# esp32-devkit-evse_2023-04-27.net
KiCad netlist of a schematic drawn in Altium Designer
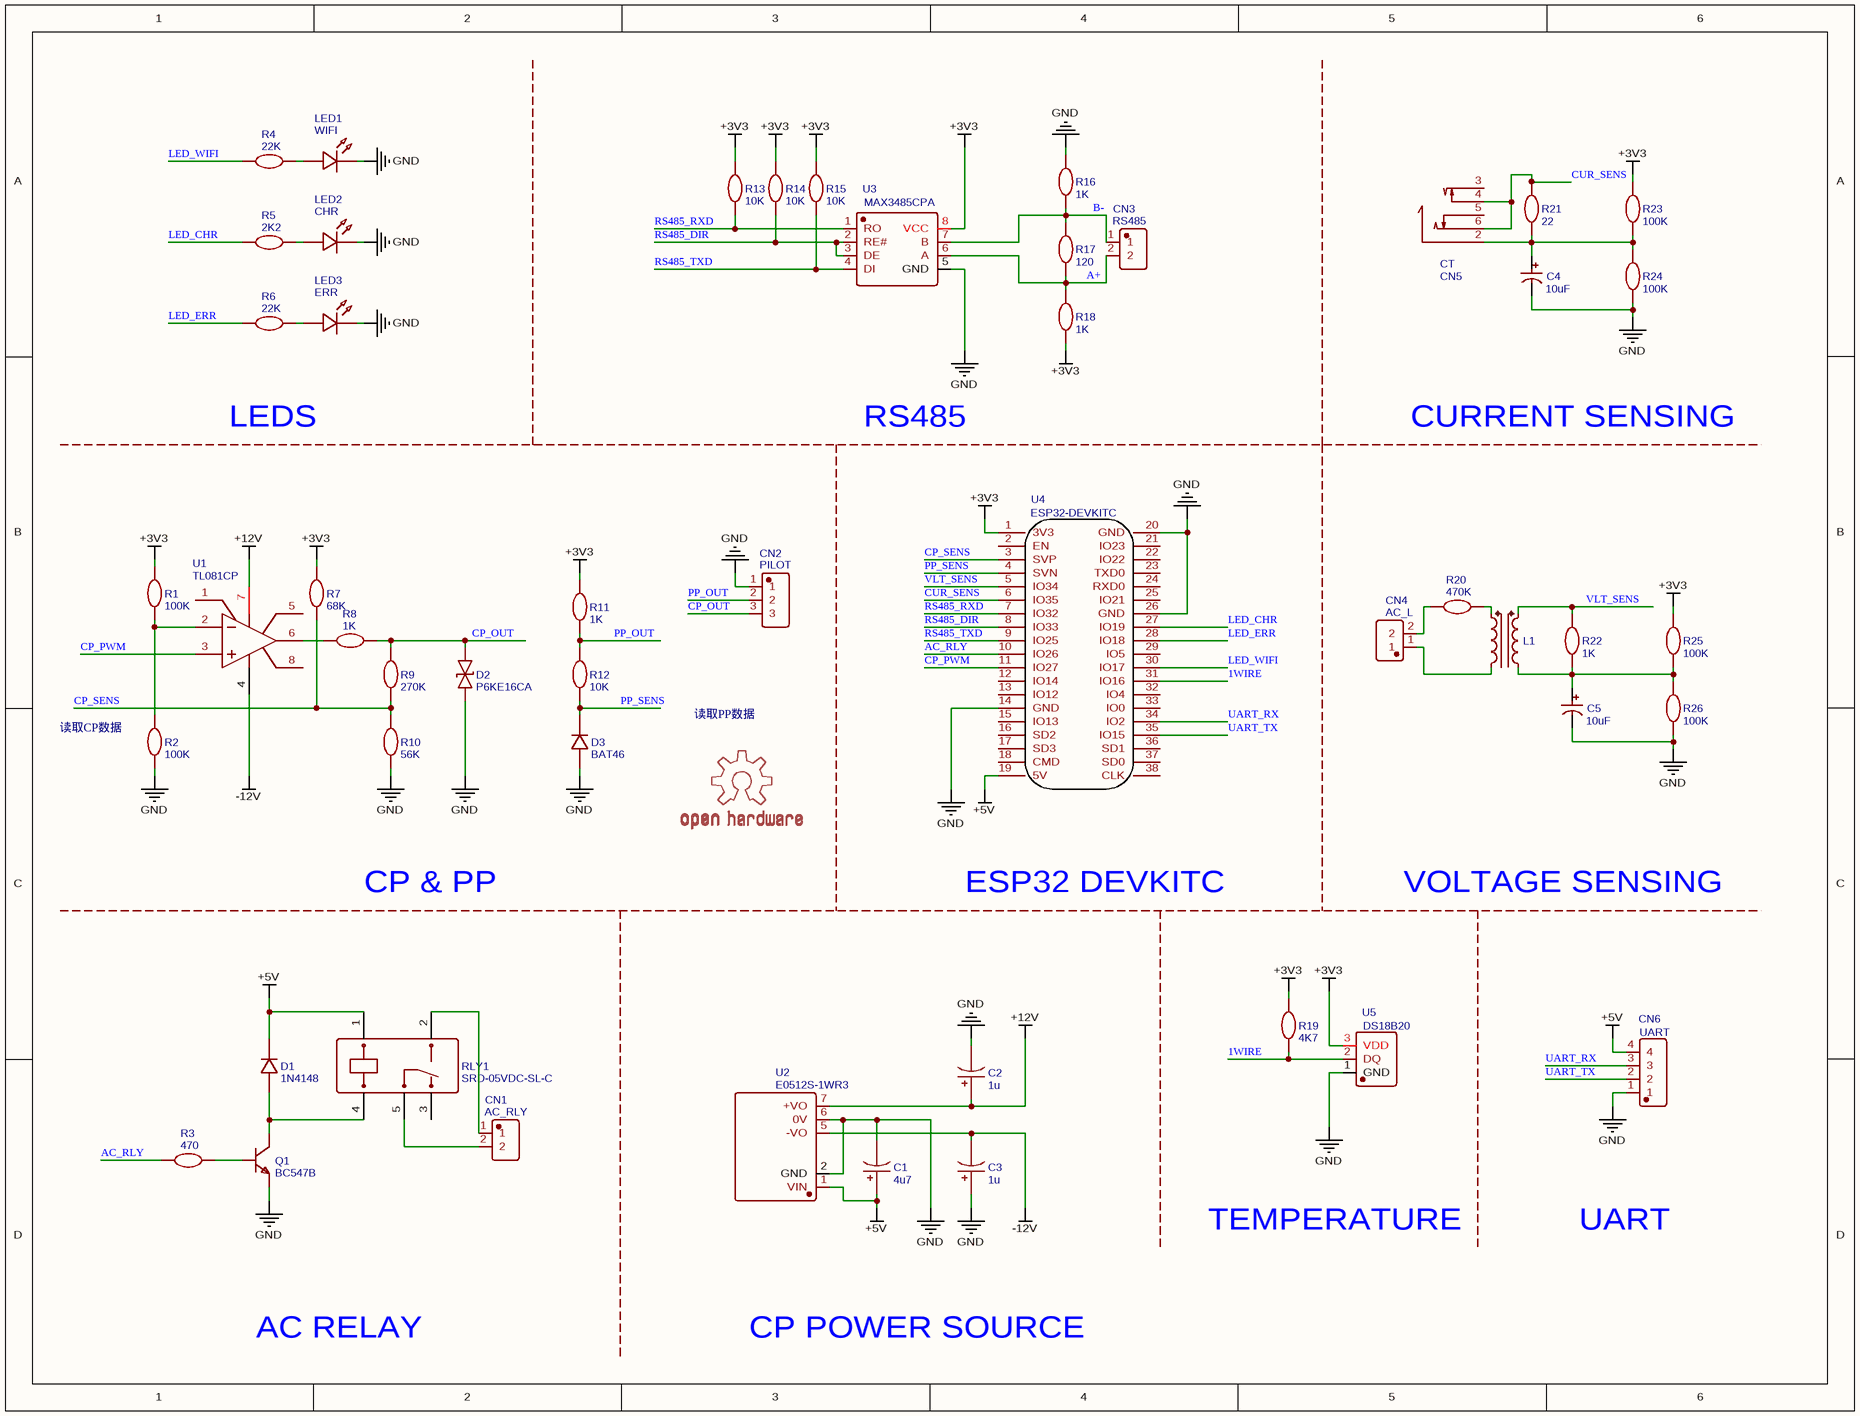
[diagram p0: esp32-devkit-evse_2023-04-27.schdoc]

(export (version "E")
  (design (tool "Eeschema 10.0.6"))
  (components
    (comp (ref "C1")
      (value "4u7")
      (footprint "CAP-D5.0×F2.0")
      (fields (field (name "CONTRIBUTOR") "LCEDA_Lib"))
      (libsource (lib "altium-import") (part "root_1_4u7_"))
    )
    (comp (ref "C2")
      (value "1u")
      (footprint "CAP-D5.0×F2.0")
      (fields (field (name "CONTRIBUTOR") "LCEDA_Lib"))
      (libsource (lib "altium-import") (part "root_1_1u_"))
    )
    (comp (ref "C3")
      (value "1u")
      (footprint "CAP-D5.0×F2.0")
      (fields (field (name "CONTRIBUTOR") "LCEDA_Lib"))
      (libsource (lib "altium-import") (part "root_1_1u_"))
    )
    (comp (ref "C4")
      (value "10uF")
      (footprint "CAP-TH_BD5.0-P2.00-D0.8-FD")
      (fields
        (field (name "BOM_MANUFACTURER PART") "10uF 25V 5*11")
        (field (name "BOM_SUPPLIER PART") "C43347")
      )
      (libsource (lib "altium-import") (part "root_3_10uF_"))
    )
    (comp (ref "C5")
      (value "10uF")
      (footprint "CAP-TH_BD5.0-P2.00-D0.8-FD")
      (fields
        (field (name "BOM_MANUFACTURER PART") "10uF 25V 5*11")
        (field (name "BOM_SUPPLIER PART") "C43347")
      )
      (libsource (lib "altium-import") (part "root_3_10uF_"))
    )
    (comp (ref "CN1")
      (value "AC_RLY")
      (footprint "CONN-TH_P5.00_KF301-5.0-2P")
      (fields
        (field (name "BOM_SUPPLIER PART") "C474881")
        (field (name "BOM_MANUFACTURER PART") "KF301-5.0-2P")
        (field (name "CONTRIBUTOR") "LCSC")
      )
      (libsource (lib "altium-import") (part "root_0_AC_RLY_"))
    )
    (comp (ref "CN2")
      (value "PILOT")
      (footprint "CONN-TH_3P-P5.00_KF301-5.0-3P")
      (fields
        (field (name "BOM_SUPPLIER PART") "C474882")
        (field (name "BOM_MANUFACTURER PART") "KF301-5.0-3P")
        (field (name "CONTRIBUTOR") "LCSC")
      )
      (libsource (lib "altium-import") (part "root_0_PILOT_"))
    )
    (comp (ref "CN3")
      (value "RS485")
      (footprint "CONN-TH_P5.00_KF301-5.0-2P")
      (fields
        (field (name "BOM_SUPPLIER PART") "C474881")
        (field (name "BOM_MANUFACTURER PART") "KF301-5.0-2P")
        (field (name "CONTRIBUTOR") "LCSC")
      )
      (libsource (lib "altium-import") (part "root_0_RS485_"))
    )
    (comp (ref "CN4")
      (value "AC_L")
      (footprint "CONN-TH_P5.00_KF301-5.0-2P")
      (fields
        (field (name "BOM_SUPPLIER PART") "C474881")
        (field (name "BOM_MANUFACTURER PART") "KF301-5.0-2P")
        (field (name "CONTRIBUTOR") "LCSC")
      )
      (libsource (lib "altium-import") (part "root_2_AC_L_"))
    )
    (comp (ref "CN5")
      (value "CT")
      (footprint "AUDIO-TH_HOOYA_PJ-358")
      (fields
        (field (name "BOM_SUPPLIER PART") "C2939193")
        (field (name "BOM_MANUFACTURER PART") "PJ-358")
        (field (name "CONTRIBUTOR") "LCSC")
      )
      (libsource (lib "altium-import") (part "root_0_CT_"))
    )
    (comp (ref "CN6")
      (value "UART")
      (footprint "CONN-TH_B4B-XH-A-G")
      (fields
        (field (name "BOM_SUPPLIER PART") "C594232")
        (field (name "BOM_MANUFACTURER PART") "B4B-XH-A-G")
        (field (name "CONTRIBUTOR") "LCSC")
      )
      (libsource (lib "altium-import") (part "root_0_UART_"))
    )
    (comp (ref "D1")
      (value "1N4148")
      (footprint "DO-35_BD2.0-L4.2-P8.20-D0.5-RD")
      (fields (field (name "BOM_SUPPLIER PART") "C13769") (field (name "CONTRIBUTOR") "LCSC"))
      (libsource (lib "altium-import") (part "root_3_1N4148_"))
    )
    (comp (ref "D2")
      (value "P6KE16CA")
      (footprint "DO-15_BD3.1-L6.7-P10.70-D0.9-BI")
      (fields (field (name "BOM_SUPPLIER PART") "C157801") (field (name "CONTRIBUTOR") "LCSC"))
      (libsource (lib "altium-import") (part "root_1_P6KE16CA_"))
    )
    (comp (ref "D3")
      (value "BAT46")
      (footprint "DO-35_BD2.0-L4.2-P8.20-D0.5-RD")
      (fields (field (name "CONTRIBUTOR") "LCSC"))
      (libsource (lib "altium-import") (part "root_3_BAT46_"))
    )
    (comp (ref "L1")
      (value "Qingxian")
      (footprint "ZMPT107-1")
      (fields
        (field (name "BOM_SUPPLIER PART") "C94572")
        (field (name "BOM_MANUFACTURER PART") "ZMPT107")
        (field (name "CONTRIBUTOR") "LCSC")
      )
      (libsource (lib "altium-import") (part "root_3_Qingxian_"))
    )
    (comp (ref "LED1")
      (value "WIFI")
      (footprint "LED-TH_BD3.0_BLUE")
      (fields
        (field (name "BOM_MANUFACTURER PART") "204-10SUBC/S400-A4")
        (field (name "BOM_SUPPLIER PART") "C86881")
        (field (name "CONTRIBUTOR") "LCEDA_Lib")
      )
      (libsource (lib "altium-import") (part "root_0_WIFI_"))
    )
    (comp (ref "LED2")
      (value "CHR")
      (footprint "LED-TH_BD3.0_GREEN")
      (fields
        (field (name "BOM_MANUFACTURER PART") "204-10SYGD/S530-E3")
        (field (name "BOM_SUPPLIER PART") "C85161")
        (field (name "CONTRIBUTOR") "LCEDA_Lib")
      )
      (libsource (lib "altium-import") (part "root_0_CHR_"))
    )
    (comp (ref "LED3")
      (value "ERR")
      (footprint "LED-TH_BD3.0_RED")
      (fields
        (field (name "BOM_MANUFACTURER PART") "204-10SDRD/S530-A3-L")
        (field (name "BOM_SUPPLIER PART") "C84774")
        (field (name "CONTRIBUTOR") "LCEDA_Lib")
      )
      (libsource (lib "altium-import") (part "root_0_ERR_"))
    )
    (comp (ref "LOGO1")
      (value "OSHW-LOGOL")
      (footprint "OSHW-LOGO-L")
      (fields (field (name "CONTRIBUTOR") "David Asassin"))
      (libsource (lib "altium-import") (part "root_0_OSHW-LOGOL_"))
    )
    (comp (ref "Q1")
      (value "BC547B")
      (footprint "TO-92-3_L4.9-W3.7-P2.54-L")
      (fields (field (name "BOM_MANUFACTURER PART") "BC547B Tube") (field (name "BOM_SUPPLIER PART") "C2092"))
      (libsource (lib "altium-import") (part "root_0_BC547B_"))
    )
    (comp (ref "R1")
      (value "100K")
      (footprint "R_AXIAL-0.4")
      (fields (field (name "CONTRIBUTOR") "LCEDA_Lib"))
      (libsource (lib "altium-import") (part "root_3_100K_"))
    )
    (comp (ref "R2")
      (value "100K")
      (footprint "R_AXIAL-0.4")
      (fields (field (name "CONTRIBUTOR") "LCEDA_Lib"))
      (libsource (lib "altium-import") (part "root_3_100K_"))
    )
    (comp (ref "R3")
      (value "470")
      (footprint "R_AXIAL-0.4")
      (fields (field (name "CONTRIBUTOR") "LCEDA_Lib"))
      (libsource (lib "altium-import") (part "root_0_470_"))
    )
    (comp (ref "R4")
      (value "22K")
      (footprint "R_AXIAL-0.4")
      (fields (field (name "CONTRIBUTOR") "LCEDA_Lib"))
      (libsource (lib "altium-import") (part "root_0_22K_"))
    )
    (comp (ref "R5")
      (value "2K2")
      (footprint "R_AXIAL-0.4")
      (fields (field (name "CONTRIBUTOR") "LCEDA_Lib"))
      (libsource (lib "altium-import") (part "root_0_2K2_"))
    )
    (comp (ref "R6")
      (value "22K")
      (footprint "R_AXIAL-0.4")
      (fields (field (name "CONTRIBUTOR") "LCEDA_Lib"))
      (libsource (lib "altium-import") (part "root_0_22K_"))
    )
    (comp (ref "R7")
      (value "68K")
      (footprint "R_AXIAL-0.4")
      (fields (field (name "CONTRIBUTOR") "LCEDA_Lib"))
      (libsource (lib "altium-import") (part "root_3_68K_"))
    )
    (comp (ref "R8")
      (value "1K")
      (footprint "R_AXIAL-0.4")
      (fields (field (name "CONTRIBUTOR") "LCEDA_Lib"))
      (libsource (lib "altium-import") (part "root_0_1K_"))
    )
    (comp (ref "R9")
      (value "270K")
      (footprint "R_AXIAL-0.4")
      (fields (field (name "CONTRIBUTOR") "LCEDA_Lib"))
      (libsource (lib "altium-import") (part "root_3_270K_"))
    )
    (comp (ref "R10")
      (value "56K")
      (footprint "R_AXIAL-0.4")
      (fields (field (name "CONTRIBUTOR") "LCEDA_Lib"))
      (libsource (lib "altium-import") (part "root_3_56K_"))
    )
    (comp (ref "R11")
      (value "1K")
      (footprint "R_AXIAL-0.4")
      (fields (field (name "CONTRIBUTOR") "LCEDA_Lib"))
      (libsource (lib "altium-import") (part "root_3_1K_"))
    )
    (comp (ref "R12")
      (value "10K")
      (footprint "R_AXIAL-0.4")
      (fields (field (name "CONTRIBUTOR") "LCEDA_Lib"))
      (libsource (lib "altium-import") (part "root_3_10K_"))
    )
    (comp (ref "R13")
      (value "10K")
      (footprint "R_AXIAL-0.4")
      (fields (field (name "CONTRIBUTOR") "LCEDA_Lib"))
      (libsource (lib "altium-import") (part "root_3_10K_"))
    )
    (comp (ref "R14")
      (value "10K")
      (footprint "R_AXIAL-0.4")
      (fields (field (name "CONTRIBUTOR") "LCEDA_Lib"))
      (libsource (lib "altium-import") (part "root_3_10K_"))
    )
    (comp (ref "R15")
      (value "10K")
      (footprint "R_AXIAL-0.4")
      (fields (field (name "CONTRIBUTOR") "LCEDA_Lib"))
      (libsource (lib "altium-import") (part "root_3_10K_"))
    )
    (comp (ref "R16")
      (value "1K")
      (footprint "R_AXIAL-0.4")
      (fields (field (name "CONTRIBUTOR") "LCEDA_Lib"))
      (libsource (lib "altium-import") (part "root_3_1K_"))
    )
    (comp (ref "R17")
      (value "120")
      (footprint "R_AXIAL-0.4")
      (fields (field (name "CONTRIBUTOR") "LCEDA_Lib"))
      (libsource (lib "altium-import") (part "root_3_120_"))
    )
    (comp (ref "R18")
      (value "1K")
      (footprint "R_AXIAL-0.4")
      (fields (field (name "CONTRIBUTOR") "LCEDA_Lib"))
      (libsource (lib "altium-import") (part "root_3_1K_"))
    )
    (comp (ref "R19")
      (value "4K7")
      (footprint "R_AXIAL-0.4")
      (fields (field (name "CONTRIBUTOR") "LCEDA_Lib"))
      (libsource (lib "altium-import") (part "root_3_4K7_"))
    )
    (comp (ref "R20")
      (value "470K")
      (footprint "R_AXIAL-0.4")
      (fields (field (name "CONTRIBUTOR") "LCEDA_Lib"))
      (libsource (lib "altium-import") (part "root_0_470K_"))
    )
    (comp (ref "R21")
      (value "22")
      (footprint "R_AXIAL-0.4")
      (fields (field (name "CONTRIBUTOR") "LCEDA_Lib"))
      (libsource (lib "altium-import") (part "root_3_22_"))
    )
    (comp (ref "R22")
      (value "1K")
      (footprint "R_AXIAL-0.4")
      (fields (field (name "CONTRIBUTOR") "LCEDA_Lib"))
      (libsource (lib "altium-import") (part "root_3_1K_"))
    )
    (comp (ref "R23")
      (value "100K")
      (footprint "R_AXIAL-0.4")
      (fields (field (name "CONTRIBUTOR") "LCEDA_Lib"))
      (libsource (lib "altium-import") (part "root_3_100K_"))
    )
    (comp (ref "R24")
      (value "100K")
      (footprint "R_AXIAL-0.4")
      (fields (field (name "CONTRIBUTOR") "LCEDA_Lib"))
      (libsource (lib "altium-import") (part "root_3_100K_"))
    )
    (comp (ref "R25")
      (value "100K")
      (footprint "R_AXIAL-0.4")
      (fields (field (name "CONTRIBUTOR") "LCEDA_Lib"))
      (libsource (lib "altium-import") (part "root_3_100K_"))
    )
    (comp (ref "R26")
      (value "100K")
      (footprint "R_AXIAL-0.4")
      (fields (field (name "CONTRIBUTOR") "LCEDA_Lib"))
      (libsource (lib "altium-import") (part "root_3_100K_"))
    )
    (comp (ref "RLY1")
      (value "SRD-05VDC-SL-C")
      (footprint "RELAY-TH_SRD-XXVDC-XL-C")
      (fields (field (name "BOM_SUPPLIER PART") "C35449"))
      (libsource (lib "altium-import") (part "root_3_SRD-05VDC-SL-C_"))
    )
    (comp (ref "U1")
      (value "TL081CP")
      (footprint "PDIP-8_L9.3-W6.4-P2.54-LS7.6-BL")
      (fields (field (name "BOM_SUPPLIER PART") "C38969"))
      (libsource (lib "altium-import") (part "root_0_TL081CP_"))
    )
    (comp (ref "U2")
      (value "E0512S-1WR3")
      (footprint "PWRM-TH_E05XXS-1WR3")
      (fields (field (name "BOM_SUPPLIER PART") "C189421") (field (name "CONTRIBUTOR") "LCSC"))
      (libsource (lib "altium-import") (part "root_2_E0512S-1WR3_"))
    )
    (comp (ref "U3")
      (value "MAX3485CPA")
      (footprint "DIP-8_L9.8-W6.6-P2.54-LS7.6-BL")
      (fields (field (name "BOM_SUPPLIER PART") "C9944"))
      (libsource (lib "altium-import") (part "root_0_MAX3485CPA_"))
    )
    (comp (ref "U4")
      (value "ESP32-DEVKITC")
      (footprint "ESP32-DEVKITC-32D")
      (fields (field (name "BOM_MANUFACTURER PART") "ESP32-DEVKITC-32D") (field (name "CONTRIBUTOR") "Ad007"))
      (libsource (lib "altium-import") (part "root_0_ESP32-DEVKITC_"))
    )
    (comp (ref "U5")
      (value "DS18B20")
      (footprint "TO-92-3_L4.9-W3.7-P2.54-L")
      (fields
        (field (name "BOM_SUPPLIER PART") "C880672")
        (field (name "BOM_MANUFACTURER PART") "DS18B20+T&R")
        (field (name "CONTRIBUTOR") "LCSC")
      )
      (libsource (lib "altium-import") (part "root_0_DS18B20_"))
    )
  )
  (nets
    (net (code "1") (name "+3V3") (class "Default")
      (node (ref "R1") (pin "1") (pinfunction "1_1") (pintype "passive"))
      (node (ref "R11") (pin "1") (pinfunction "1_1") (pintype "passive"))
      (node (ref "R13") (pin "1") (pinfunction "1_1") (pintype "passive"))
      (node (ref "R14") (pin "1") (pinfunction "1_1") (pintype "passive"))
      (node (ref "R15") (pin "1") (pinfunction "1_1") (pintype "passive"))
      (node (ref "R18") (pin "2") (pinfunction "2_2") (pintype "passive"))
      (node (ref "R19") (pin "1") (pinfunction "1_1") (pintype "passive"))
      (node (ref "R23") (pin "1") (pinfunction "1_1") (pintype "passive"))
      (node (ref "R25") (pin "1") (pinfunction "1_1") (pintype "passive"))
      (node (ref "R7") (pin "1") (pinfunction "1_1") (pintype "passive"))
      (node (ref "U3") (pin "8") (pinfunction "VCC_8") (pintype "passive"))
      (node (ref "U4") (pin "1") (pinfunction "3V3_1") (pintype "passive"))
      (node (ref "U5") (pin "3") (pinfunction "VDD_3") (pintype "passive"))
    )
    (net (code "2") (name "+5V") (class "Default")
      (node (ref "C1") (pin "1") (pinfunction "1_1") (pintype "passive"))
      (node (ref "CN6") (pin "4") (pinfunction "4_4") (pintype "passive"))
      (node (ref "D1") (pin "1") (pinfunction "1_1") (pintype "passive"))
      (node (ref "RLY1") (pin "1") (pinfunction "1_1") (pintype "passive"))
      (node (ref "U2") (pin "1") (pinfunction "VIN_1") (pintype "passive"))
      (node (ref "U4") (pin "19") (pinfunction "5V_19") (pintype "passive"))
    )
    (net (code "3") (name "+12V") (class "Default")
      (node (ref "C2") (pin "1") (pinfunction "1_1") (pintype "passive"))
      (node (ref "U1") (pin "7") (pinfunction "V+_7") (pintype "passive"))
      (node (ref "U2") (pin "7") (pinfunction "+VO_7") (pintype "passive"))
    )
    (net (code "4") (name "-12V") (class "Default")
      (node (ref "C3") (pin "2") (pinfunction "2_2") (pintype "passive"))
      (node (ref "U1") (pin "4") (pinfunction "V-_4") (pintype "passive"))
      (node (ref "U2") (pin "5") (pinfunction "-VO_5") (pintype "passive"))
    )
    (net (code "5") (name "/1WIRE") (class "Default")
      (node (ref "R19") (pin "2") (pinfunction "2_2") (pintype "passive"))
      (node (ref "U4") (pin "31") (pinfunction "IO16_31") (pintype "passive"))
      (node (ref "U5") (pin "2") (pinfunction "DQ_2") (pintype "passive"))
    )
    (net (code "6") (name "/A+") (class "Default")
      (node (ref "CN3") (pin "2") (pinfunction "2_2") (pintype "passive"))
      (node (ref "R17") (pin "2") (pinfunction "2_2") (pintype "passive"))
      (node (ref "R18") (pin "1") (pinfunction "1_1") (pintype "passive"))
      (node (ref "U3") (pin "6") (pinfunction "A_6") (pintype "passive"))
    )
    (net (code "7") (name "/AC_RLY") (class "Default")
      (node (ref "R3") (pin "1") (pinfunction "1_1") (pintype "passive"))
      (node (ref "U4") (pin "10") (pinfunction "IO26_10") (pintype "passive"))
    )
    (net (code "8") (name "/B-") (class "Default")
      (node (ref "CN3") (pin "1") (pinfunction "1_1") (pintype "passive"))
      (node (ref "R16") (pin "2") (pinfunction "2_2") (pintype "passive"))
      (node (ref "R17") (pin "1") (pinfunction "1_1") (pintype "passive"))
      (node (ref "U3") (pin "7") (pinfunction "B_7") (pintype "passive"))
    )
    (net (code "9") (name "/CP_OUT") (class "Default")
      (node (ref "CN2") (pin "3") (pinfunction "3_3") (pintype "passive"))
      (node (ref "D2") (pin "2") (pinfunction "A_2") (pintype "passive"))
      (node (ref "R8") (pin "2") (pinfunction "2_2") (pintype "passive"))
      (node (ref "R9") (pin "1") (pinfunction "1_1") (pintype "passive"))
    )
    (net (code "10") (name "/CP_PWM") (class "Default")
      (node (ref "U1") (pin "3") (pinfunction "IN+_3") (pintype "passive"))
      (node (ref "U4") (pin "11") (pinfunction "IO27_11") (pintype "passive"))
    )
    (net (code "11") (name "/CP_SENS") (class "Default")
      (node (ref "R10") (pin "1") (pinfunction "1_1") (pintype "passive"))
      (node (ref "R7") (pin "2") (pinfunction "2_2") (pintype "passive"))
      (node (ref "R9") (pin "2") (pinfunction "2_2") (pintype "passive"))
      (node (ref "U4") (pin "3") (pinfunction "SVP_3") (pintype "passive"))
    )
    (net (code "12") (name "/CUR_SENS") (class "Default")
      (node (ref "CN5") (pin "4") (pinfunction "4_4") (pintype "passive"))
      (node (ref "CN5") (pin "6") (pinfunction "6_6") (pintype "passive"))
      (node (ref "R21") (pin "1") (pinfunction "1_1") (pintype "passive"))
      (node (ref "U4") (pin "6") (pinfunction "IO35_6") (pintype "passive"))
    )
    (net (code "13") (name "/LED_CHR") (class "Default")
      (node (ref "R5") (pin "1") (pinfunction "1_1") (pintype "passive"))
      (node (ref "U4") (pin "27") (pinfunction "IO19_27") (pintype "passive"))
    )
    (net (code "14") (name "/LED_ERR") (class "Default")
      (node (ref "R6") (pin "1") (pinfunction "1_1") (pintype "passive"))
      (node (ref "U4") (pin "28") (pinfunction "IO18_28") (pintype "passive"))
    )
    (net (code "15") (name "/LED_WIFI") (class "Default")
      (node (ref "R4") (pin "1") (pinfunction "1_1") (pintype "passive"))
      (node (ref "U4") (pin "30") (pinfunction "IO17_30") (pintype "passive"))
    )
    (net (code "16") (name "/PP_OUT") (class "Default")
      (node (ref "CN2") (pin "2") (pinfunction "2_2") (pintype "passive"))
      (node (ref "R11") (pin "2") (pinfunction "2_2") (pintype "passive"))
      (node (ref "R12") (pin "1") (pinfunction "1_1") (pintype "passive"))
    )
    (net (code "17") (name "/PP_SENS") (class "Default")
      (node (ref "D3") (pin "1") (pinfunction "1_1") (pintype "passive"))
      (node (ref "R12") (pin "2") (pinfunction "2_2") (pintype "passive"))
      (node (ref "U4") (pin "4") (pinfunction "SVN_4") (pintype "passive"))
    )
    (net (code "18") (name "/RS485_DIR") (class "Default")
      (node (ref "R14") (pin "2") (pinfunction "2_2") (pintype "passive"))
      (node (ref "U3") (pin "2") (pinfunction "RE#_2") (pintype "passive"))
      (node (ref "U3") (pin "3") (pinfunction "DE_3") (pintype "passive"))
      (node (ref "U4") (pin "8") (pinfunction "IO33_8") (pintype "passive"))
    )
    (net (code "19") (name "/RS485_RXD") (class "Default")
      (node (ref "R13") (pin "2") (pinfunction "2_2") (pintype "passive"))
      (node (ref "U3") (pin "1") (pinfunction "RO_1") (pintype "passive"))
      (node (ref "U4") (pin "7") (pinfunction "IO32_7") (pintype "passive"))
    )
    (net (code "20") (name "/RS485_TXD") (class "Default")
      (node (ref "R15") (pin "2") (pinfunction "2_2") (pintype "passive"))
      (node (ref "U3") (pin "4") (pinfunction "DI_4") (pintype "passive"))
      (node (ref "U4") (pin "9") (pinfunction "IO25_9") (pintype "passive"))
    )
    (net (code "21") (name "/UART_RX") (class "Default")
      (node (ref "CN6") (pin "3") (pinfunction "3_3") (pintype "passive"))
      (node (ref "U4") (pin "34") (pinfunction "IO2_34") (pintype "passive"))
    )
    (net (code "22") (name "/UART_TX") (class "Default")
      (node (ref "CN6") (pin "2") (pinfunction "2_2") (pintype "passive"))
      (node (ref "U4") (pin "35") (pinfunction "IO15_35") (pintype "passive"))
    )
    (net (code "23") (name "/VLT_SENS") (class "Default")
      (node (ref "L1") (pin "1") (pinfunction "1_1") (pintype "passive"))
      (node (ref "R22") (pin "1") (pinfunction "1_1") (pintype "passive"))
      (node (ref "U4") (pin "5") (pinfunction "IO34_5") (pintype "passive"))
    )
    (net (code "24") (name "GND") (class "Default")
      (node (ref "C1") (pin "2") (pinfunction "2_2") (pintype "passive"))
      (node (ref "C2") (pin "2") (pinfunction "2_2") (pintype "passive"))
      (node (ref "C3") (pin "1") (pinfunction "1_1") (pintype "passive"))
      (node (ref "C4") (pin "2") (pinfunction "2_2") (pintype "passive"))
      (node (ref "C5") (pin "2") (pinfunction "2_2") (pintype "passive"))
      (node (ref "CN2") (pin "1") (pinfunction "1_1") (pintype "passive"))
      (node (ref "CN6") (pin "1") (pinfunction "1_1") (pintype "passive"))
      (node (ref "D2") (pin "1") (pinfunction "K_1") (pintype "passive"))
      (node (ref "D3") (pin "2") (pinfunction "2_2") (pintype "passive"))
      (node (ref "LED1") (pin "2") (pinfunction "2_2") (pintype "passive"))
      (node (ref "LED2") (pin "2") (pinfunction "2_2") (pintype "passive"))
      (node (ref "LED3") (pin "2") (pinfunction "2_2") (pintype "passive"))
      (node (ref "Q1") (pin "3") (pinfunction "E_3") (pintype "passive"))
      (node (ref "R10") (pin "2") (pinfunction "2_2") (pintype "passive"))
      (node (ref "R16") (pin "1") (pinfunction "1_1") (pintype "passive"))
      (node (ref "R2") (pin "2") (pinfunction "2_2") (pintype "passive"))
      (node (ref "R24") (pin "2") (pinfunction "2_2") (pintype "passive"))
      (node (ref "R26") (pin "2") (pinfunction "2_2") (pintype "passive"))
      (node (ref "U2") (pin "2") (pinfunction "GND_2") (pintype "passive"))
      (node (ref "U2") (pin "6") (pinfunction "0V_6") (pintype "passive"))
      (node (ref "U3") (pin "5") (pinfunction "GND_5") (pintype "passive"))
      (node (ref "U4") (pin "14") (pinfunction "GND_14") (pintype "passive"))
      (node (ref "U4") (pin "20") (pinfunction "GND_20") (pintype "passive"))
      (node (ref "U4") (pin "26") (pinfunction "GND_26") (pintype "passive"))
      (node (ref "U5") (pin "1") (pinfunction "GND_1") (pintype "passive"))
    )
    (net (code "25") (name "Net-(C4-Pad1)") (class "Default")
      (node (ref "C4") (pin "1") (pinfunction "1_1") (pintype "passive"))
      (node (ref "CN5") (pin "2") (pinfunction "2_2") (pintype "passive"))
      (node (ref "R21") (pin "2") (pinfunction "2_2") (pintype "passive"))
      (node (ref "R23") (pin "2") (pinfunction "2_2") (pintype "passive"))
      (node (ref "R24") (pin "1") (pinfunction "1_1") (pintype "passive"))
    )
    (net (code "26") (name "Net-(C5-Pad1)") (class "Default")
      (node (ref "C5") (pin "1") (pinfunction "1_1") (pintype "passive"))
      (node (ref "L1") (pin "2") (pinfunction "2_2") (pintype "passive"))
      (node (ref "R22") (pin "2") (pinfunction "2_2") (pintype "passive"))
      (node (ref "R25") (pin "2") (pinfunction "2_2") (pintype "passive"))
      (node (ref "R26") (pin "1") (pinfunction "1_1") (pintype "passive"))
    )
    (net (code "27") (name "Net-(CN1-Pad1)") (class "Default")
      (node (ref "CN1") (pin "1") (pinfunction "1_1") (pintype "passive"))
      (node (ref "RLY1") (pin "2") (pinfunction "2_2") (pintype "passive"))
    )
    (net (code "28") (name "Net-(CN1-Pad2)") (class "Default")
      (node (ref "CN1") (pin "2") (pinfunction "2_2") (pintype "passive"))
      (node (ref "RLY1") (pin "5") (pinfunction "5_5") (pintype "passive"))
    )
    (net (code "29") (name "Net-(CN4-Pad1)") (class "Default")
      (node (ref "CN4") (pin "1") (pinfunction "1_1") (pintype "passive"))
      (node (ref "L1") (pin "4") (pinfunction "4_4") (pintype "passive"))
    )
    (net (code "30") (name "Net-(CN4-Pad2)") (class "Default")
      (node (ref "CN4") (pin "2") (pinfunction "2_2") (pintype "passive"))
      (node (ref "R20") (pin "1") (pinfunction "1_1") (pintype "passive"))
    )
    (net (code "31") (name "Net-(L1-Pad3)") (class "Default")
      (node (ref "L1") (pin "3") (pinfunction "3_3") (pintype "passive"))
      (node (ref "R20") (pin "2") (pinfunction "2_2") (pintype "passive"))
    )
    (net (code "32") (name "Net-(LED1-Pad1)") (class "Default")
      (node (ref "LED1") (pin "1") (pinfunction "1_1") (pintype "passive"))
      (node (ref "R4") (pin "2") (pinfunction "2_2") (pintype "passive"))
    )
    (net (code "33") (name "Net-(LED2-Pad1)") (class "Default")
      (node (ref "LED2") (pin "1") (pinfunction "1_1") (pintype "passive"))
      (node (ref "R5") (pin "2") (pinfunction "2_2") (pintype "passive"))
    )
    (net (code "34") (name "Net-(LED3-Pad1)") (class "Default")
      (node (ref "LED3") (pin "1") (pinfunction "1_1") (pintype "passive"))
      (node (ref "R6") (pin "2") (pinfunction "2_2") (pintype "passive"))
    )
    (net (code "35") (name "Net-(Q1-B)") (class "Default")
      (node (ref "Q1") (pin "2") (pinfunction "B_2") (pintype "passive"))
      (node (ref "R3") (pin "2") (pinfunction "2_2") (pintype "passive"))
    )
    (net (code "36") (name "Net-(Q1-C)") (class "Default")
      (node (ref "D1") (pin "2") (pinfunction "2_2") (pintype "passive"))
      (node (ref "Q1") (pin "1") (pinfunction "C_1") (pintype "passive"))
      (node (ref "RLY1") (pin "4") (pinfunction "4_4") (pintype "passive"))
    )
    (net (code "37") (name "Net-(U1-IN-)") (class "Default")
      (node (ref "R1") (pin "2") (pinfunction "2_2") (pintype "passive"))
      (node (ref "R2") (pin "1") (pinfunction "1_1") (pintype "passive"))
      (node (ref "U1") (pin "2") (pinfunction "IN-_2") (pintype "passive"))
    )
    (net (code "38") (name "Net-(U1-OUT)") (class "Default")
      (node (ref "R8") (pin "1") (pinfunction "1_1") (pintype "passive"))
      (node (ref "U1") (pin "6") (pinfunction "OUT_6") (pintype "passive"))
    )
    (net (code "39") (name "unconnected-(CN5-Pad3)") (class "Default")
      (node (ref "CN5") (pin "3") (pinfunction "3_3") (pintype "passive"))
    )
    (net (code "40") (name "unconnected-(CN5-Pad5)") (class "Default")
      (node (ref "CN5") (pin "5") (pinfunction "5_5") (pintype "passive"))
    )
    (net (code "41") (name "unconnected-(RLY1-Pad3)") (class "Default")
      (node (ref "RLY1") (pin "3") (pinfunction "3_3") (pintype "passive"))
    )
    (net (code "42") (name "unconnected-(U1-NC-Pad8)") (class "Default")
      (node (ref "U1") (pin "8") (pinfunction "NC_8") (pintype "passive"))
    )
    (net (code "43") (name "unconnected-(U1-OS_NULL-Pad1)") (class "Default")
      (node (ref "U1") (pin "1") (pinfunction "OS_NULL_1") (pintype "passive"))
    )
    (net (code "44") (name "unconnected-(U1-OS_NULL-Pad5)") (class "Default")
      (node (ref "U1") (pin "5") (pinfunction "OS_NULL_5") (pintype "passive"))
    )
    (net (code "45") (name "unconnected-(U4-CLK-Pad38)") (class "Default")
      (node (ref "U4") (pin "38") (pinfunction "CLK_38") (pintype "passive"))
    )
    (net (code "46") (name "unconnected-(U4-CMD-Pad18)") (class "Default")
      (node (ref "U4") (pin "18") (pinfunction "CMD_18") (pintype "passive"))
    )
    (net (code "47") (name "unconnected-(U4-EN-Pad2)") (class "Default")
      (node (ref "U4") (pin "2") (pinfunction "EN_2") (pintype "passive"))
    )
    (net (code "48") (name "unconnected-(U4-IO0-Pad33)") (class "Default")
      (node (ref "U4") (pin "33") (pinfunction "IO0_33") (pintype "passive"))
    )
    (net (code "49") (name "unconnected-(U4-IO4-Pad32)") (class "Default")
      (node (ref "U4") (pin "32") (pinfunction "IO4_32") (pintype "passive"))
    )
    (net (code "50") (name "unconnected-(U4-IO5-Pad29)") (class "Default")
      (node (ref "U4") (pin "29") (pinfunction "IO5_29") (pintype "passive"))
    )
    (net (code "51") (name "unconnected-(U4-IO12-Pad13)") (class "Default")
      (node (ref "U4") (pin "13") (pinfunction "IO12_13") (pintype "passive"))
    )
    (net (code "52") (name "unconnected-(U4-IO13-Pad15)") (class "Default")
      (node (ref "U4") (pin "15") (pinfunction "IO13_15") (pintype "passive"))
    )
    (net (code "53") (name "unconnected-(U4-IO14-Pad12)") (class "Default")
      (node (ref "U4") (pin "12") (pinfunction "IO14_12") (pintype "passive"))
    )
    (net (code "54") (name "unconnected-(U4-IO21-Pad25)") (class "Default")
      (node (ref "U4") (pin "25") (pinfunction "IO21_25") (pintype "passive"))
    )
    (net (code "55") (name "unconnected-(U4-IO22-Pad22)") (class "Default")
      (node (ref "U4") (pin "22") (pinfunction "IO22_22") (pintype "passive"))
    )
    (net (code "56") (name "unconnected-(U4-IO23-Pad21)") (class "Default")
      (node (ref "U4") (pin "21") (pinfunction "IO23_21") (pintype "passive"))
    )
    (net (code "57") (name "unconnected-(U4-RXD0-Pad24)") (class "Default")
      (node (ref "U4") (pin "24") (pinfunction "RXD0_24") (pintype "passive"))
    )
    (net (code "58") (name "unconnected-(U4-SD0-Pad37)") (class "Default")
      (node (ref "U4") (pin "37") (pinfunction "SD0_37") (pintype "passive"))
    )
    (net (code "59") (name "unconnected-(U4-SD1-Pad36)") (class "Default")
      (node (ref "U4") (pin "36") (pinfunction "SD1_36") (pintype "passive"))
    )
    (net (code "60") (name "unconnected-(U4-SD2-Pad16)") (class "Default")
      (node (ref "U4") (pin "16") (pinfunction "SD2_16") (pintype "passive"))
    )
    (net (code "61") (name "unconnected-(U4-SD3-Pad17)") (class "Default")
      (node (ref "U4") (pin "17") (pinfunction "SD3_17") (pintype "passive"))
    )
    (net (code "62") (name "unconnected-(U4-TXD0-Pad23)") (class "Default")
      (node (ref "U4") (pin "23") (pinfunction "TXD0_23") (pintype "passive"))
    )
  )
)
